# SymphonyLights_MCU_v1_1.net
KiCad netlist of a schematic drawn in Altium Designer
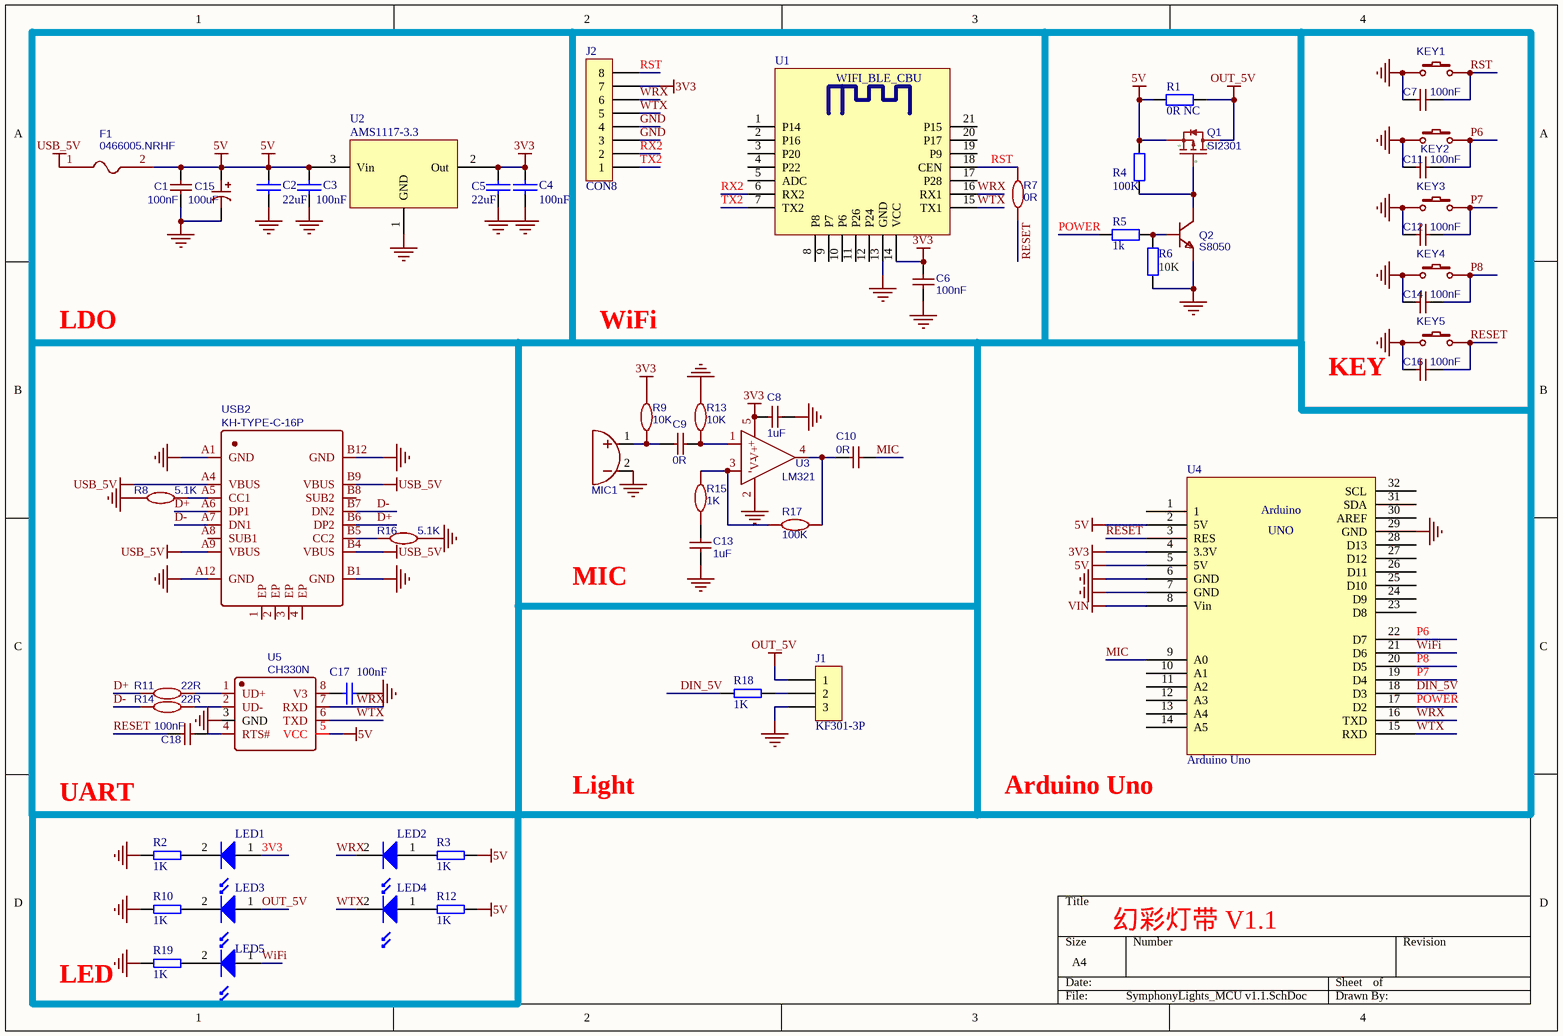
[diagram p0: SymphonyLights_MCU v1.1.SchDoc]

(export (version "E")
  (design (tool "Eeschema 10.0.6"))
  (components
    (comp (ref "C1")
      (value "100nF")
      (footprint "0805C")
      (fields
        (field (name "BOM_MANUFACTURER PART") "0805B104K500NT")
        (field (name "BOM_SUPPLIER PART") "C38141")
      )
      (libsource (lib "altium-import") (part "root_1_100nF_"))
    )
    (comp (ref "C2")
      (value "22uF")
      (footprint "0805C")
      (description "Capacitor")
      (libsource (lib "昊华元件库sch") (part "CAP"))
    )
    (comp (ref "C3")
      (value "100nF")
      (footprint "0805C")
      (description "Capacitor")
      (libsource (lib "昊华元件库sch") (part "CAP"))
    )
    (comp (ref "C4")
      (value "100nF")
      (footprint "0805C")
      (description "Capacitor")
      (libsource (lib "昊华元件库sch") (part "CAP"))
    )
    (comp (ref "C5")
      (value "22uF")
      (footprint "0805C")
      (description "Capacitor")
      (libsource (lib "昊华元件库sch") (part "CAP"))
    )
    (comp (ref "C6")
      (value "100nF")
      (footprint "0805C")
      (fields
        (field (name "BOM_MANUFACTURER PART") "0805B104K500NT")
        (field (name "BOM_SUPPLIER PART") "C38141")
      )
      (libsource (lib "altium-import") (part "root_1_100nF_"))
    )
    (comp (ref "C7")
      (value "100nF")
      (footprint "0805C")
      (fields
        (field (name "BOM_MANUFACTURER PART") "0805B104K500NT")
        (field (name "BOM_SUPPLIER PART") "C38141")
      )
      (libsource (lib "altium-import") (part "root_0_100nF_"))
    )
    (comp (ref "C8")
      (value "1uF")
      (footprint "0805C")
      (fields
        (field (name "BOM_MANUFACTURER PART") "0805B104K500NT")
        (field (name "BOM_SUPPLIER PART") "C38141")
      )
      (libsource (lib "altium-import") (part "root_0_100nF_"))
    )
    (comp (ref "C9")
      (value "0R")
      (footprint "0805C")
      (fields
        (field (name "BOM_MANUFACTURER PART") "0805B104K500NT")
        (field (name "BOM_SUPPLIER PART") "C38141")
      )
      (libsource (lib "altium-import") (part "root_2_100nF_"))
    )
    (comp (ref "C10")
      (value "0R")
      (footprint "0805C")
      (fields
        (field (name "BOM_MANUFACTURER PART") "0805B104K500NT")
        (field (name "BOM_SUPPLIER PART") "C38141")
      )
      (libsource (lib "altium-import") (part "root_2_100nF_"))
    )
    (comp (ref "C11")
      (value "100nF")
      (footprint "0805C")
      (fields
        (field (name "BOM_MANUFACTURER PART") "0805B104K500NT")
        (field (name "BOM_SUPPLIER PART") "C38141")
      )
      (libsource (lib "altium-import") (part "root_0_100nF_"))
    )
    (comp (ref "C12")
      (value "100nF")
      (footprint "0805C")
      (fields
        (field (name "BOM_MANUFACTURER PART") "0805B104K500NT")
        (field (name "BOM_SUPPLIER PART") "C38141")
      )
      (libsource (lib "altium-import") (part "root_0_100nF_"))
    )
    (comp (ref "C13")
      (value "1uF")
      (footprint "0805C")
      (fields
        (field (name "BOM_MANUFACTURER PART") "0805B104K500NT")
        (field (name "BOM_SUPPLIER PART") "C38141")
      )
      (libsource (lib "altium-import") (part "root_3_100nF_"))
    )
    (comp (ref "C14")
      (value "100nF")
      (footprint "0805C")
      (fields
        (field (name "BOM_MANUFACTURER PART") "0805B104K500NT")
        (field (name "BOM_SUPPLIER PART") "C38141")
      )
      (libsource (lib "altium-import") (part "root_0_100nF_"))
    )
    (comp (ref "C15")
      (value "100uF")
      (footprint "CAP-TH_BD6.3-P2.50-D1.0-FD")
      (fields
        (field (name "BOM_SUPPLIER PART") "C723077")
        (field (name "BOM_MANUFACTURER PART") "8101LCMAA08E2RR00O")
        (field (name "CONTRIBUTOR") "LCSC")
      )
      (libsource (lib "altium-import") (part "root_3_8101LCMAA08E2RR00O_"))
    )
    (comp (ref "C16")
      (value "100nF")
      (footprint "0805C")
      (fields
        (field (name "BOM_MANUFACTURER PART") "0805B104K500NT")
        (field (name "BOM_SUPPLIER PART") "C38141")
      )
      (libsource (lib "altium-import") (part "root_0_100nF_"))
    )
    (comp (ref "C17")
      (value "100nF")
      (footprint "0805C")
      (description "普通电容")
      (libsource (lib "RFID_RC632") (part "Cap"))
    )
    (comp (ref "C18")
      (value "100nF")
      (footprint "0805C")
      (fields
        (field (name "BOM_MANUFACTURER PART") "0805B104K500NT")
        (field (name "BOM_SUPPLIER PART") "C38141")
      )
      (libsource (lib "altium-import") (part "root_0_100nF_"))
    )
    (comp (ref "F1")
      (value "0466005.NRHF")
      (footprint "1206F")
      (fields (field (name "BOM_SUPPLIER PART") "C57525"))
      (libsource (lib "altium-import") (part "root_0_0466005.NRHF_"))
    )
    (comp (ref "J1")
      (value "KF301-3P")
      (footprint "SIP3 - 2.54")
      (description "Connector")
      (libsource (lib "小马元件库sch") (part "CON3"))
    )
    (comp (ref "J2")
      (value "CON8")
      (footprint "HDR1X8Z")
      (description "Connector")
      (libsource (lib "小马元件库sch") (part "CON8"))
    )
    (comp (ref "KEY1")
      (value "RESET")
      (footprint "按键")
      (fields
        (field (name "BOM_SUPPLIER PART") "C118141")
        (field (name "BOM_MANUFACTURER PART") "K2-1107ST-A4SW-06")
        (field (name "CONTRIBUTOR") "LCEDA_Lib")
      )
      (libsource (lib "altium-import") (part "root_2_mirrored__"))
    )
    (comp (ref "KEY2")
      (value "场景")
      (footprint "按键")
      (fields
        (field (name "BOM_SUPPLIER PART") "C118141")
        (field (name "BOM_MANUFACTURER PART") "K2-1107ST-A4SW-06")
        (field (name "CONTRIBUTOR") "LCEDA_Lib")
      )
      (libsource (lib "altium-import") (part "root_2__"))
    )
    (comp (ref "KEY3")
      (value "音乐")
      (footprint "按键")
      (fields
        (field (name "BOM_SUPPLIER PART") "C118141")
        (field (name "BOM_MANUFACTURER PART") "K2-1107ST-A4SW-06")
        (field (name "CONTRIBUTOR") "LCEDA_Lib")
      )
      (libsource (lib "altium-import") (part "root_2_mirrored__"))
    )
    (comp (ref "KEY4")
      (value "开关")
      (footprint "按键")
      (fields
        (field (name "BOM_SUPPLIER PART") "C118141")
        (field (name "BOM_MANUFACTURER PART") "K2-1107ST-A4SW-06")
        (field (name "CONTRIBUTOR") "LCEDA_Lib")
      )
      (libsource (lib "altium-import") (part "root_2_mirrored__"))
    )
    (comp (ref "KEY5")
      (value "开关")
      (footprint "按键")
      (fields
        (field (name "BOM_SUPPLIER PART") "C118141")
        (field (name "BOM_MANUFACTURER PART") "K2-1107ST-A4SW-06")
        (field (name "CONTRIBUTOR") "LCEDA_Lib")
      )
      (libsource (lib "altium-import") (part "root_2_mirrored__"))
    )
    (comp (ref "LED1")
      (value "LED")
      (footprint "0805LED")
      (fields (field (name "PUBLISHER") "*"))
      (libsource (lib "小马元件库sch") (part "LED"))
    )
    (comp (ref "LED2")
      (value "LED")
      (footprint "0805LED")
      (fields (field (name "PUBLISHER") "*"))
      (libsource (lib "小马元件库sch") (part "LED"))
    )
    (comp (ref "LED3")
      (value "LED")
      (footprint "0805LED")
      (fields (field (name "PUBLISHER") "*"))
      (libsource (lib "小马元件库sch") (part "LED"))
    )
    (comp (ref "LED4")
      (value "LED")
      (footprint "0805LED")
      (fields (field (name "PUBLISHER") "*"))
      (libsource (lib "小马元件库sch") (part "LED"))
    )
    (comp (ref "LED5")
      (value "LED")
      (footprint "0805LED")
      (fields (field (name "PUBLISHER") "*"))
      (libsource (lib "小马元件库sch") (part "LED"))
    )
    (comp (ref "MIC1")
      (value "GMI6050P-66DB")
      (footprint "MIC-TH_BD6.0-P1.90-D0.4-L-RD")
      (fields (field (name "BOM_SUPPLIER PART") "C233954") (field (name "CONTRIBUTOR") "LCSC"))
      (libsource (lib "altium-import") (part "root_3_mirrored_GMI6050P-66DB_"))
    )
    (comp (ref "Q1")
      (value "SI2301")
      (footprint "SOT-23(SOT-23-3)")
      (fields (field (name "BOM_SUPPLIER PART") "C181086") (field (name "CONTRIBUTOR") "lengyuefeng"))
      (libsource (lib "altium-import") (part "root_1_mirrored_SI2301_"))
    )
    (comp (ref "Q2")
      (value "S8050")
      (footprint "SOT-23(SOT-23-3)")
      (fields (field (name "BOM_SUPPLIER PART") "C2146"))
      (libsource (lib "altium-import") (part "root_0_S8050_"))
    )
    (comp (ref "R1")
      (value "0R NC")
      (footprint "0805R")
      (description "Resistor")
      (fields (field (name "PUBLISHER") "Altium Limited"))
      (libsource (lib "*") (part "Res2"))
    )
    (comp (ref "R2") (value "1K") (footprint "0805R") (libsource (lib "昊华元件库sch") (part "RES5")))
    (comp (ref "R3") (value "1K") (footprint "0805R") (libsource (lib "昊华元件库sch") (part "RES5")))
    (comp (ref "R4")
      (value "100K")
      (footprint "0805R")
      (description "Resistor")
      (fields (field (name "PUBLISHER") "Altium Limited"))
      (libsource (lib "") (part "Res2_2"))
    )
    (comp (ref "R5")
      (value "1k")
      (footprint "0805R")
      (description "Resistor")
      (fields (field (name "PUBLISHER") "Altium Limited"))
      (libsource (lib "*") (part "Res2"))
    )
    (comp (ref "R6")
      (value "10K")
      (footprint "0805R")
      (description "Resistor")
      (fields (field (name "PUBLISHER") "Altium Limited"))
      (libsource (lib "") (part "Res2_1"))
    )
    (comp (ref "R7")
      (value "0R")
      (footprint "0805R")
      (fields
        (field (name "BOM_SUPPLIER PART") "C328298")
        (field (name "BOM_MANUFACTURER PART") "AECR0402F10K0K9")
        (field (name "CONTRIBUTOR") "LCSC")
      )
      (libsource (lib "altium-import") (part "root_3_10K_"))
    )
    (comp (ref "R8")
      (value "5.1K")
      (footprint "0805R")
      (fields
        (field (name "BOM_SUPPLIER PART") "C328298")
        (field (name "BOM_MANUFACTURER PART") "AECR0402F10K0K9")
        (field (name "CONTRIBUTOR") "LCSC")
      )
      (libsource (lib "altium-import") (part "root_0_10K_"))
    )
    (comp (ref "R9")
      (value "10K")
      (footprint "0805R")
      (fields
        (field (name "BOM_SUPPLIER PART") "C328298")
        (field (name "BOM_MANUFACTURER PART") "AECR0402F10K0K9")
        (field (name "CONTRIBUTOR") "LCSC")
      )
      (libsource (lib "altium-import") (part "root_3_10K_"))
    )
    (comp (ref "R10") (value "1K") (footprint "0805R") (libsource (lib "昊华元件库sch") (part "RES5")))
    (comp (ref "R11")
      (value "22R")
      (footprint "0805R")
      (fields
        (field (name "BOM_SUPPLIER PART") "C328298")
        (field (name "BOM_MANUFACTURER PART") "AECR0402F10K0K9")
        (field (name "CONTRIBUTOR") "LCSC")
      )
      (libsource (lib "altium-import") (part "root_2_10K_"))
    )
    (comp (ref "R12") (value "1K") (footprint "0805R") (libsource (lib "昊华元件库sch") (part "RES5")))
    (comp (ref "R13")
      (value "10K")
      (footprint "0805R")
      (fields
        (field (name "BOM_SUPPLIER PART") "C328298")
        (field (name "BOM_MANUFACTURER PART") "AECR0402F10K0K9")
        (field (name "CONTRIBUTOR") "LCSC")
      )
      (libsource (lib "altium-import") (part "root_3_10K_"))
    )
    (comp (ref "R14")
      (value "22R")
      (footprint "0805R")
      (fields
        (field (name "BOM_SUPPLIER PART") "C328298")
        (field (name "BOM_MANUFACTURER PART") "AECR0402F10K0K9")
        (field (name "CONTRIBUTOR") "LCSC")
      )
      (libsource (lib "altium-import") (part "root_2_10K_"))
    )
    (comp (ref "R15")
      (value "1K")
      (footprint "0805R")
      (fields
        (field (name "BOM_SUPPLIER PART") "C328298")
        (field (name "BOM_MANUFACTURER PART") "AECR0402F10K0K9")
        (field (name "CONTRIBUTOR") "LCSC")
      )
      (libsource (lib "altium-import") (part "root_1_10K_"))
    )
    (comp (ref "R16")
      (value "5.1K")
      (footprint "0805R")
      (fields
        (field (name "BOM_SUPPLIER PART") "C328298")
        (field (name "BOM_MANUFACTURER PART") "AECR0402F10K0K9")
        (field (name "CONTRIBUTOR") "LCSC")
      )
      (libsource (lib "altium-import") (part "root_2_10K_"))
    )
    (comp (ref "R17")
      (value "100K")
      (footprint "0805R")
      (fields
        (field (name "BOM_SUPPLIER PART") "C328298")
        (field (name "BOM_MANUFACTURER PART") "AECR0402F10K0K9")
        (field (name "CONTRIBUTOR") "LCSC")
      )
      (libsource (lib "altium-import") (part "root_0_10K_"))
    )
    (comp (ref "R18") (value "1K") (footprint "0805R") (libsource (lib "昊华元件库sch") (part "RES5")))
    (comp (ref "R19") (value "1K") (footprint "0805R") (libsource (lib "昊华元件库sch") (part "RES5")))
    (comp (ref "U1")
      (value "WIFI_BLE_CBU")
      (footprint "WIFI_BLE_CBU")
      (description "Module")
      (libsource (lib "TYModeSchlib V03") (part "WIFI_BLE_CBU"))
    )
    (comp (ref "U2") (value "AMS1117-3.3") (footprint "SOT-223") (libsource (lib "mylib") (part "GM1117")))
    (comp (ref "U3")
      (value "LM321")
      (footprint "SOT-23-5")
      (fields (field (name "CONTRIBUTOR") "KiCAD"))
      (libsource (lib "altium-import") (part "root_0_LM321_"))
    )
    (comp (ref "U4")
      (value "Arduino Uno")
      (footprint "Arduino UNO-2")
      (libsource (lib "Arduino") (part "Arduino Uno"))
    )
    (comp (ref "U5")
      (value "CH330N")
      (footprint "SOP-8_L4.9-W3.9-P1.27-LS6.0-BL")
      (fields (field (name "BOM_SUPPLIER PART") "C108996"))
      (libsource (lib "altium-import") (part "root_0_CH330N_"))
    )
    (comp (ref "USB2")
      (value "KH-TYPE-C-16P")
      (footprint "USB-C-SMD_KH-TYPE-C-16P")
      (fields (field (name "BOM_SUPPLIER PART") "C709357") (field (name "CONTRIBUTOR") "LCSC"))
      (libsource (lib "altium-import") (part "root_0_KH-TYPE-C-16P_"))
    )
  )
  (nets
    (net (code "1") (name "/D+") (class "Default")
      (node (ref "R11") (pin "2") (pinfunction "2_2") (pintype "passive"))
      (node (ref "USB2") (pin "A6") (pinfunction "DP1_A6") (pintype "passive"))
      (node (ref "USB2") (pin "B6") (pinfunction "DP2_B6") (pintype "passive"))
    )
    (net (code "2") (name "/D-") (class "Default")
      (node (ref "R14") (pin "2") (pinfunction "2_2") (pintype "passive"))
      (node (ref "USB2") (pin "A7") (pinfunction "DN1_A7") (pintype "passive"))
      (node (ref "USB2") (pin "B7") (pinfunction "DN2_B7") (pintype "passive"))
    )
    (net (code "3") (name "/DIN_5V") (class "Default")
      (node (ref "R18") (pin "1") (pinfunction "1_1") (pintype "passive"))
      (node (ref "U4") (pin "18") (pinfunction "D3_18") (pintype "passive"))
    )
    (net (code "4") (name "/MIC") (class "Default")
      (node (ref "C10") (pin "1") (pinfunction "1_1") (pintype "passive"))
      (node (ref "U4") (pin "9") (pinfunction "A0_9") (pintype "passive"))
    )
    (net (code "5") (name "/P6") (class "Default")
      (node (ref "C11") (pin "2") (pinfunction "2_2") (pintype "passive"))
      (node (ref "KEY2") (pin "2") (pinfunction "2_2") (pintype "passive"))
      (node (ref "U4") (pin "22") (pinfunction "D7_22") (pintype "passive"))
    )
    (net (code "6") (name "/P7") (class "Default")
      (node (ref "C12") (pin "2") (pinfunction "2_2") (pintype "passive"))
      (node (ref "KEY3") (pin "1") (pinfunction "1_1") (pintype "passive"))
      (node (ref "U4") (pin "19") (pinfunction "D4_19") (pintype "passive"))
    )
    (net (code "7") (name "/P8") (class "Default")
      (node (ref "C14") (pin "2") (pinfunction "2_2") (pintype "passive"))
      (node (ref "KEY4") (pin "1") (pinfunction "1_1") (pintype "passive"))
      (node (ref "U4") (pin "20") (pinfunction "D5_20") (pintype "passive"))
    )
    (net (code "8") (name "/POWER") (class "Default")
      (node (ref "R5") (pin "1") (pinfunction "1_1") (pintype "passive"))
      (node (ref "U4") (pin "17") (pinfunction "D2_17") (pintype "passive"))
    )
    (net (code "9") (name "/RESET") (class "Default")
      (node (ref "C16") (pin "2") (pinfunction "2_2") (pintype "passive"))
      (node (ref "C18") (pin "1") (pinfunction "1_1") (pintype "passive"))
      (node (ref "KEY5") (pin "1") (pinfunction "1_1") (pintype "passive"))
      (node (ref "R7") (pin "2") (pinfunction "2_2") (pintype "passive"))
      (node (ref "U4") (pin "3") (pinfunction "RES_3") (pintype "passive"))
    )
    (net (code "10") (name "/RST") (class "Default")
      (node (ref "C7") (pin "2") (pinfunction "2_2") (pintype "passive"))
      (node (ref "J2") (pin "8") (pinfunction "8_8") (pintype "passive"))
      (node (ref "KEY1") (pin "1") (pinfunction "1_1") (pintype "passive"))
      (node (ref "R7") (pin "1") (pinfunction "1_1") (pintype "passive"))
      (node (ref "U1") (pin "18") (pinfunction "CEN_18") (pintype "passive"))
    )
    (net (code "11") (name "/RX2") (class "Default")
      (node (ref "J2") (pin "2") (pinfunction "2_2") (pintype "passive"))
      (node (ref "U1") (pin "6") (pinfunction "RX2_6") (pintype "passive"))
    )
    (net (code "12") (name "/TX2") (class "Default")
      (node (ref "J2") (pin "1") (pinfunction "1_1") (pintype "passive"))
      (node (ref "U1") (pin "7") (pinfunction "TX2_7") (pintype "passive"))
    )
    (net (code "13") (name "/WRX") (class "Default")
      (node (ref "J2") (pin "6") (pinfunction "6_6") (pintype "passive"))
      (node (ref "LED2") (pin "2") (pinfunction "2_2") (pintype "passive"))
      (node (ref "U1") (pin "16") (pinfunction "RX1_16") (pintype "passive"))
      (node (ref "U4") (pin "16") (pinfunction "TXD_16") (pintype "passive"))
      (node (ref "U5") (pin "7") (pinfunction "RXD_7") (pintype "passive"))
    )
    (net (code "14") (name "/WTX") (class "Default")
      (node (ref "J2") (pin "5") (pinfunction "5_5") (pintype "passive"))
      (node (ref "LED4") (pin "2") (pinfunction "2_2") (pintype "passive"))
      (node (ref "U1") (pin "15") (pinfunction "TX1_15") (pintype "passive"))
      (node (ref "U4") (pin "15") (pinfunction "RXD_15") (pintype "passive"))
      (node (ref "U5") (pin "6") (pinfunction "TXD_6") (pintype "passive"))
    )
    (net (code "15") (name "/WiFi") (class "Default")
      (node (ref "LED5") (pin "1") (pinfunction "1_1") (pintype "passive"))
      (node (ref "U4") (pin "21") (pinfunction "D6_21") (pintype "passive"))
    )
    (net (code "16") (name "3V3") (class "Default")
      (node (ref "C4") (pin "1") (pinfunction "1_1") (pintype "passive"))
      (node (ref "C5") (pin "1") (pinfunction "1_1") (pintype "passive"))
      (node (ref "C6") (pin "2") (pinfunction "2_2") (pintype "passive"))
      (node (ref "C8") (pin "1") (pinfunction "1_1") (pintype "passive"))
      (node (ref "J2") (pin "7") (pinfunction "7_7") (pintype "passive"))
      (node (ref "LED1") (pin "1") (pinfunction "1_1") (pintype "passive"))
      (node (ref "R9") (pin "1") (pinfunction "1_1") (pintype "passive"))
      (node (ref "U1") (pin "14") (pinfunction "VCC_14") (pintype "passive"))
      (node (ref "U2") (pin "2") (pinfunction "Out_2") (pintype "passive"))
      (node (ref "U3") (pin "5") (pinfunction "V+_5") (pintype "passive"))
      (node (ref "U4") (pin "4") (pinfunction "3.3V_4") (pintype "passive"))
    )
    (net (code "17") (name "5V") (class "Default")
      (node (ref "C1") (pin "2") (pinfunction "2_2") (pintype "passive"))
      (node (ref "C15") (pin "1") (pinfunction "1_1") (pintype "passive"))
      (node (ref "C2") (pin "1") (pinfunction "1_1") (pintype "passive"))
      (node (ref "C3") (pin "1") (pinfunction "1_1") (pintype "passive"))
      (node (ref "F1") (pin "2") (pinfunction "2_2") (pintype "passive"))
      (node (ref "Q1") (pin "2") (pinfunction "S_2") (pintype "passive"))
      (node (ref "R1") (pin "1") (pinfunction "1_1") (pintype "passive"))
      (node (ref "R12") (pin "1") (pinfunction "1_1") (pintype "passive"))
      (node (ref "R3") (pin "1") (pinfunction "1_1") (pintype "passive"))
      (node (ref "R4") (pin "2") (pinfunction "2_2") (pintype "passive"))
      (node (ref "U2") (pin "3") (pinfunction "Vin_3") (pintype "passive"))
      (node (ref "U4") (pin "2") (pinfunction "5V_2") (pintype "passive"))
      (node (ref "U4") (pin "5") (pinfunction "5V_5") (pintype "passive"))
      (node (ref "U5") (pin "5") (pinfunction "VCC_5") (pintype "passive"))
    )
    (net (code "18") (name "GND") (class "Default")
      (node (ref "C1") (pin "1") (pinfunction "1_1") (pintype "passive"))
      (node (ref "C11") (pin "1") (pinfunction "1_1") (pintype "passive"))
      (node (ref "C12") (pin "1") (pinfunction "1_1") (pintype "passive"))
      (node (ref "C13") (pin "2") (pinfunction "2_2") (pintype "passive"))
      (node (ref "C14") (pin "1") (pinfunction "1_1") (pintype "passive"))
      (node (ref "C15") (pin "2") (pinfunction "2_2") (pintype "passive"))
      (node (ref "C16") (pin "1") (pinfunction "1_1") (pintype "passive"))
      (node (ref "C17") (pin "1") (pinfunction "1_1") (pintype "passive"))
      (node (ref "C2") (pin "2") (pinfunction "2_2") (pintype "passive"))
      (node (ref "C3") (pin "2") (pinfunction "2_2") (pintype "passive"))
      (node (ref "C4") (pin "2") (pinfunction "2_2") (pintype "passive"))
      (node (ref "C5") (pin "2") (pinfunction "2_2") (pintype "passive"))
      (node (ref "C6") (pin "1") (pinfunction "1_1") (pintype "passive"))
      (node (ref "C7") (pin "1") (pinfunction "1_1") (pintype "passive"))
      (node (ref "C8") (pin "2") (pinfunction "2_2") (pintype "passive"))
      (node (ref "J1") (pin "3") (pinfunction "3_3") (pintype "passive"))
      (node (ref "J2") (pin "3") (pinfunction "3_3") (pintype "passive"))
      (node (ref "J2") (pin "4") (pinfunction "4_4") (pintype "passive"))
      (node (ref "KEY1") (pin "2") (pinfunction "2_2") (pintype "passive"))
      (node (ref "KEY2") (pin "1") (pinfunction "1_1") (pintype "passive"))
      (node (ref "KEY3") (pin "2") (pinfunction "2_2") (pintype "passive"))
      (node (ref "KEY4") (pin "2") (pinfunction "2_2") (pintype "passive"))
      (node (ref "KEY5") (pin "2") (pinfunction "2_2") (pintype "passive"))
      (node (ref "MIC1") (pin "2") (pinfunction "2_2") (pintype "passive"))
      (node (ref "Q2") (pin "2") (pinfunction "E_2") (pintype "passive"))
      (node (ref "R10") (pin "2") (pinfunction "2_2") (pintype "passive"))
      (node (ref "R13") (pin "1") (pinfunction "1_1") (pintype "passive"))
      (node (ref "R16") (pin "1") (pinfunction "1_1") (pintype "passive"))
      (node (ref "R19") (pin "2") (pinfunction "2_2") (pintype "passive"))
      (node (ref "R2") (pin "2") (pinfunction "2_2") (pintype "passive"))
      (node (ref "R6") (pin "2") (pinfunction "2_2") (pintype "passive"))
      (node (ref "R8") (pin "1") (pinfunction "1_1") (pintype "passive"))
      (node (ref "U1") (pin "13") (pinfunction "GND_13") (pintype "passive"))
      (node (ref "U2") (pin "1") (pinfunction "GND_1") (pintype "passive"))
      (node (ref "U3") (pin "2") (pinfunction "V-_2") (pintype "passive"))
      (node (ref "U4") (pin "29") (pinfunction "GND_29") (pintype "passive"))
      (node (ref "U4") (pin "6") (pinfunction "GND_6") (pintype "passive"))
      (node (ref "U4") (pin "7") (pinfunction "GND_7") (pintype "passive"))
      (node (ref "U5") (pin "3") (pinfunction "GND_3") (pintype "passive"))
      (node (ref "USB2") (pin "A1") (pinfunction "GND_A1") (pintype "passive"))
      (node (ref "USB2") (pin "A12") (pinfunction "GND_A12") (pintype "passive"))
      (node (ref "USB2") (pin "B1") (pinfunction "GND_B1") (pintype "passive"))
      (node (ref "USB2") (pin "B12") (pinfunction "GND_B12") (pintype "passive"))
    )
    (net (code "19") (name "Net-(C9-Pad2)") (class "Default")
      (node (ref "C9") (pin "2") (pinfunction "2_2") (pintype "passive"))
      (node (ref "MIC1") (pin "1") (pinfunction "1_1") (pintype "passive"))
      (node (ref "R9") (pin "2") (pinfunction "2_2") (pintype "passive"))
    )
    (net (code "20") (name "Net-(C10-Pad2)") (class "Default")
      (node (ref "C10") (pin "2") (pinfunction "2_2") (pintype "passive"))
      (node (ref "R17") (pin "2") (pinfunction "2_2") (pintype "passive"))
      (node (ref "U3") (pin "4") (pintype "passive"))
    )
    (net (code "21") (name "Net-(C13-Pad1)") (class "Default")
      (node (ref "C13") (pin "1") (pinfunction "1_1") (pintype "passive"))
      (node (ref "R15") (pin "1") (pinfunction "1_1") (pintype "passive"))
    )
    (net (code "22") (name "Net-(J1-Pad2)") (class "Default")
      (node (ref "J1") (pin "2") (pinfunction "2_2") (pintype "passive"))
      (node (ref "R18") (pin "2") (pinfunction "2_2") (pintype "passive"))
    )
    (net (code "23") (name "Net-(LED1-Pad2)") (class "Default")
      (node (ref "LED1") (pin "2") (pinfunction "2_2") (pintype "passive"))
      (node (ref "R2") (pin "1") (pinfunction "1_1") (pintype "passive"))
    )
    (net (code "24") (name "Net-(LED2-Pad1)") (class "Default")
      (node (ref "LED2") (pin "1") (pinfunction "1_1") (pintype "passive"))
      (node (ref "R3") (pin "2") (pinfunction "2_2") (pintype "passive"))
    )
    (net (code "25") (name "Net-(LED3-Pad2)") (class "Default")
      (node (ref "LED3") (pin "2") (pinfunction "2_2") (pintype "passive"))
      (node (ref "R10") (pin "1") (pinfunction "1_1") (pintype "passive"))
    )
    (net (code "26") (name "Net-(LED4-Pad1)") (class "Default")
      (node (ref "LED4") (pin "1") (pinfunction "1_1") (pintype "passive"))
      (node (ref "R12") (pin "2") (pinfunction "2_2") (pintype "passive"))
    )
    (net (code "27") (name "Net-(LED5-Pad2)") (class "Default")
      (node (ref "LED5") (pin "2") (pinfunction "2_2") (pintype "passive"))
      (node (ref "R19") (pin "1") (pinfunction "1_1") (pintype "passive"))
    )
    (net (code "28") (name "Net-(Q1-G)") (class "Default")
      (node (ref "Q1") (pin "1") (pinfunction "G_1") (pintype "passive"))
      (node (ref "Q2") (pin "3") (pinfunction "C_3") (pintype "passive"))
      (node (ref "R4") (pin "1") (pinfunction "1_1") (pintype "passive"))
    )
    (net (code "29") (name "Net-(Q2-B)") (class "Default")
      (node (ref "Q2") (pin "1") (pinfunction "B_1") (pintype "passive"))
      (node (ref "R5") (pin "2") (pinfunction "2_2") (pintype "passive"))
      (node (ref "R6") (pin "1") (pinfunction "1_1") (pintype "passive"))
    )
    (net (code "30") (name "Net-(U3-+)") (class "Default")
      (node (ref "C9") (pin "1") (pinfunction "1_1") (pintype "passive"))
      (node (ref "R13") (pin "2") (pinfunction "2_2") (pintype "passive"))
      (node (ref "U3") (pin "1") (pinfunction "+_1") (pintype "passive"))
    )
    (net (code "31") (name "Net-(U3--)") (class "Default")
      (node (ref "R15") (pin "2") (pinfunction "2_2") (pintype "passive"))
      (node (ref "R17") (pin "1") (pinfunction "1_1") (pintype "passive"))
      (node (ref "U3") (pin "3") (pinfunction "-_3") (pintype "passive"))
    )
    (net (code "32") (name "Net-(U5-RTS#)") (class "Default")
      (node (ref "C18") (pin "2") (pinfunction "2_2") (pintype "passive"))
      (node (ref "U5") (pin "4") (pinfunction "RTS#_4") (pintype "passive"))
    )
    (net (code "33") (name "Net-(U5-UD+)") (class "Default")
      (node (ref "R11") (pin "1") (pinfunction "1_1") (pintype "passive"))
      (node (ref "U5") (pin "1") (pinfunction "UD+_1") (pintype "passive"))
    )
    (net (code "34") (name "Net-(U5-UD-)") (class "Default")
      (node (ref "R14") (pin "1") (pinfunction "1_1") (pintype "passive"))
      (node (ref "U5") (pin "2") (pinfunction "UD-_2") (pintype "passive"))
    )
    (net (code "35") (name "Net-(U5-V3)") (class "Default")
      (node (ref "C17") (pin "2") (pinfunction "2_2") (pintype "passive"))
      (node (ref "U5") (pin "8") (pinfunction "V3_8") (pintype "passive"))
    )
    (net (code "36") (name "Net-(USB2-CC1)") (class "Default")
      (node (ref "R8") (pin "2") (pinfunction "2_2") (pintype "passive"))
      (node (ref "USB2") (pin "A5") (pinfunction "CC1_A5") (pintype "passive"))
    )
    (net (code "37") (name "Net-(USB2-CC2)") (class "Default")
      (node (ref "R16") (pin "2") (pinfunction "2_2") (pintype "passive"))
      (node (ref "USB2") (pin "B5") (pinfunction "CC2_B5") (pintype "passive"))
    )
    (net (code "38") (name "OUT_5V") (class "Default")
      (node (ref "J1") (pin "1") (pinfunction "1_1") (pintype "passive"))
      (node (ref "LED3") (pin "1") (pinfunction "1_1") (pintype "passive"))
      (node (ref "Q1") (pin "3") (pinfunction "D_3") (pintype "passive"))
      (node (ref "R1") (pin "2") (pinfunction "2_2") (pintype "passive"))
    )
    (net (code "39") (name "USB_5V") (class "Default")
      (node (ref "F1") (pin "1") (pinfunction "1_1") (pintype "passive"))
      (node (ref "USB2") (pin "A4") (pinfunction "VBUS_A4") (pintype "passive"))
      (node (ref "USB2") (pin "A9") (pinfunction "VBUS_A9") (pintype "passive"))
      (node (ref "USB2") (pin "B4") (pinfunction "VBUS_B4") (pintype "passive"))
      (node (ref "USB2") (pin "B9") (pinfunction "VBUS_B9") (pintype "passive"))
    )
    (net (code "40") (name "VIN") (class "Default")
      (node (ref "U4") (pin "8") (pinfunction "Vin_8") (pintype "passive"))
    )
    (net (code "41") (name "unconnected-(U1-ADC-Pad5)") (class "Default")
      (node (ref "U1") (pin "5") (pinfunction "ADC_5") (pintype "passive"))
    )
    (net (code "42") (name "unconnected-(U1-P6-Pad10)") (class "Default")
      (node (ref "U1") (pin "10") (pinfunction "P6_10") (pintype "passive"))
    )
    (net (code "43") (name "unconnected-(U1-P7-Pad9)") (class "Default")
      (node (ref "U1") (pin "9") (pinfunction "P7_9") (pintype "passive"))
    )
    (net (code "44") (name "unconnected-(U1-P8-Pad8)") (class "Default")
      (node (ref "U1") (pin "8") (pinfunction "P8_8") (pintype "passive"))
    )
    (net (code "45") (name "unconnected-(U1-P9-Pad19)") (class "Default")
      (node (ref "U1") (pin "19") (pinfunction "P9_19") (pintype "passive"))
    )
    (net (code "46") (name "unconnected-(U1-P14-Pad1)") (class "Default")
      (node (ref "U1") (pin "1") (pinfunction "P14_1") (pintype "passive"))
    )
    (net (code "47") (name "unconnected-(U1-P15-Pad21)") (class "Default")
      (node (ref "U1") (pin "21") (pinfunction "P15_21") (pintype "passive"))
    )
    (net (code "48") (name "unconnected-(U1-P16-Pad2)") (class "Default")
      (node (ref "U1") (pin "2") (pinfunction "P16_2") (pintype "passive"))
    )
    (net (code "49") (name "unconnected-(U1-P17-Pad20)") (class "Default")
      (node (ref "U1") (pin "20") (pinfunction "P17_20") (pintype "passive"))
    )
    (net (code "50") (name "unconnected-(U1-P20-Pad3)") (class "Default")
      (node (ref "U1") (pin "3") (pinfunction "P20_3") (pintype "passive"))
    )
    (net (code "51") (name "unconnected-(U1-P22-Pad4)") (class "Default")
      (node (ref "U1") (pin "4") (pinfunction "P22_4") (pintype "passive"))
    )
    (net (code "52") (name "unconnected-(U1-P24-Pad12)") (class "Default")
      (node (ref "U1") (pin "12") (pinfunction "P24_12") (pintype "passive"))
    )
    (net (code "53") (name "unconnected-(U1-P26-Pad11)") (class "Default")
      (node (ref "U1") (pin "11") (pinfunction "P26_11") (pintype "passive"))
    )
    (net (code "54") (name "unconnected-(U1-P28-Pad17)") (class "Default")
      (node (ref "U1") (pin "17") (pinfunction "P28_17") (pintype "passive"))
    )
    (net (code "55") (name "unconnected-(U4-A1-Pad10)") (class "Default")
      (node (ref "U4") (pin "10") (pinfunction "A1_10") (pintype "passive"))
    )
    (net (code "56") (name "unconnected-(U4-A2-Pad11)") (class "Default")
      (node (ref "U4") (pin "11") (pinfunction "A2_11") (pintype "passive"))
    )
    (net (code "57") (name "unconnected-(U4-A3-Pad12)") (class "Default")
      (node (ref "U4") (pin "12") (pinfunction "A3_12") (pintype "passive"))
    )
    (net (code "58") (name "unconnected-(U4-A4-Pad13)") (class "Default")
      (node (ref "U4") (pin "13") (pinfunction "A4_13") (pintype "passive"))
    )
    (net (code "59") (name "unconnected-(U4-A5-Pad14)") (class "Default")
      (node (ref "U4") (pin "14") (pinfunction "A5_14") (pintype "passive"))
    )
    (net (code "60") (name "unconnected-(U4-AREF-Pad30)") (class "Default")
      (node (ref "U4") (pin "30") (pinfunction "AREF_30") (pintype "passive"))
    )
    (net (code "61") (name "unconnected-(U4-D8-Pad23)") (class "Default")
      (node (ref "U4") (pin "23") (pinfunction "D8_23") (pintype "passive"))
    )
    (net (code "62") (name "unconnected-(U4-D9-Pad24)") (class "Default")
      (node (ref "U4") (pin "24") (pinfunction "D9_24") (pintype "passive"))
    )
    (net (code "63") (name "unconnected-(U4-D10-Pad25)") (class "Default")
      (node (ref "U4") (pin "25") (pinfunction "D10_25") (pintype "passive"))
    )
    (net (code "64") (name "unconnected-(U4-D11-Pad26)") (class "Default")
      (node (ref "U4") (pin "26") (pinfunction "D11_26") (pintype "passive"))
    )
    (net (code "65") (name "unconnected-(U4-D12-Pad27)") (class "Default")
      (node (ref "U4") (pin "27") (pinfunction "D12_27") (pintype "passive"))
    )
    (net (code "66") (name "unconnected-(U4-D13-Pad28)") (class "Default")
      (node (ref "U4") (pin "28") (pinfunction "D13_28") (pintype "passive"))
    )
    (net (code "67") (name "unconnected-(U4-Pad1)") (class "Default")
      (node (ref "U4") (pin "1") (pinfunction "1_1") (pintype "passive"))
    )
    (net (code "68") (name "unconnected-(U4-SCL-Pad32)") (class "Default")
      (node (ref "U4") (pin "32") (pinfunction "SCL_32") (pintype "passive"))
    )
    (net (code "69") (name "unconnected-(U4-SDA-Pad31)") (class "Default")
      (node (ref "U4") (pin "31") (pinfunction "SDA_31") (pintype "passive"))
    )
    (net (code "70") (name "unconnected-(USB2-EP-Pad1)") (class "Default")
      (node (ref "USB2") (pin "1") (pinfunction "EP_1") (pintype "passive"))
    )
    (net (code "71") (name "unconnected-(USB2-EP-Pad2)") (class "Default")
      (node (ref "USB2") (pin "2") (pinfunction "EP_2") (pintype "passive"))
    )
    (net (code "72") (name "unconnected-(USB2-EP-Pad3)") (class "Default")
      (node (ref "USB2") (pin "3") (pinfunction "EP_3") (pintype "passive"))
    )
    (net (code "73") (name "unconnected-(USB2-EP-Pad4)") (class "Default")
      (node (ref "USB2") (pin "4") (pinfunction "EP_4") (pintype "passive"))
    )
    (net (code "74") (name "unconnected-(USB2-SUB1-PadA8)") (class "Default")
      (node (ref "USB2") (pin "A8") (pinfunction "SUB1_A8") (pintype "passive"))
    )
    (net (code "75") (name "unconnected-(USB2-SUB2-PadB8)") (class "Default")
      (node (ref "USB2") (pin "B8") (pinfunction "SUB2_B8") (pintype "passive"))
    )
  )
)
